# Optocoupler.net
KiCad netlist of a schematic drawn in Altium Designer
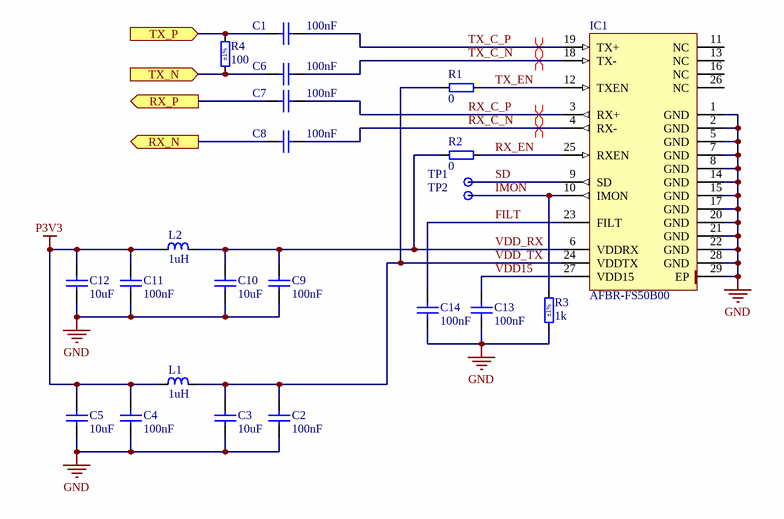
[diagram p0: Optocoupler.SchDoc]

(export (version "E")
  (design (tool "Eeschema 10.0.6"))
  (components
    (comp (ref "C1")
      (value "100nF")
      (footprint "CAPC1005X55N")
      (description "Non-polarised capacitor")
      (fields
        (field (name "PART NUMBER") "CC0402_100NF_50V_10%_X7R")
        (field (name "VOLTAGE") "50V")
        (field (name "AUTHOR") "CERN DEM MR")
      )
      (libsource (lib "Capacitors") (part "Capacitor - non polarized"))
    )
    (comp (ref "C2")
      (value "100nF")
      (footprint "CAPC1005X55N")
      (description "Non-polarised capacitor")
      (fields
        (field (name "PART NUMBER") "CC0402_100NF_50V_10%_X7R")
        (field (name "VOLTAGE") "50V")
        (field (name "AUTHOR") "CERN DEM MR")
      )
      (libsource (lib "Capacitors") (part "Capacitor - non polarized"))
    )
    (comp (ref "C3")
      (value "10uF")
      (footprint "CAPC1005X55N")
      (description "SMD Mulitlayer Ceramic Chip Capacitor")
      (fields
        (field (name "PART NUMBER") "CC0402_10UF_6.3V_20%_X5R")
        (field (name "VOLTAGE") "6.3V")
        (field (name "AUTHOR") "Michal Beldyga")
      )
      (libsource (lib "Capacitors") (part "Capacitor - non polarized"))
    )
    (comp (ref "C4")
      (value "100nF")
      (footprint "CAPC1005X55N")
      (description "Non-polarised capacitor")
      (fields
        (field (name "PART NUMBER") "CC0402_100NF_50V_10%_X7R")
        (field (name "VOLTAGE") "50V")
        (field (name "AUTHOR") "CERN DEM MR")
      )
      (libsource (lib "Capacitors") (part "Capacitor - non polarized"))
    )
    (comp (ref "C5")
      (value "10uF")
      (footprint "CAPC1005X55N")
      (description "SMD Mulitlayer Ceramic Chip Capacitor")
      (fields
        (field (name "PART NUMBER") "CC0402_10UF_6.3V_20%_X5R")
        (field (name "VOLTAGE") "6.3V")
        (field (name "AUTHOR") "Michal Beldyga")
      )
      (libsource (lib "Capacitors") (part "Capacitor - non polarized"))
    )
    (comp (ref "C6")
      (value "100nF")
      (footprint "CAPC1005X55N")
      (description "Non-polarised capacitor")
      (fields
        (field (name "PART NUMBER") "CC0402_100NF_50V_10%_X7R")
        (field (name "VOLTAGE") "50V")
        (field (name "AUTHOR") "CERN DEM MR")
      )
      (libsource (lib "Capacitors") (part "Capacitor - non polarized"))
    )
    (comp (ref "C7")
      (value "100nF")
      (footprint "CAPC1005X55N")
      (description "Non-polarised capacitor")
      (fields
        (field (name "PART NUMBER") "CC0402_100NF_50V_10%_X7R")
        (field (name "VOLTAGE") "50V")
        (field (name "AUTHOR") "CERN DEM MR")
      )
      (libsource (lib "Capacitors") (part "Capacitor - non polarized"))
    )
    (comp (ref "C8")
      (value "100nF")
      (footprint "CAPC1005X55N")
      (description "Non-polarised capacitor")
      (fields
        (field (name "PART NUMBER") "CC0402_100NF_50V_10%_X7R")
        (field (name "VOLTAGE") "50V")
        (field (name "AUTHOR") "CERN DEM MR")
      )
      (libsource (lib "Capacitors") (part "Capacitor - non polarized"))
    )
    (comp (ref "C9")
      (value "100nF")
      (footprint "CAPC1005X55N")
      (description "Non-polarised capacitor")
      (fields
        (field (name "PART NUMBER") "CC0402_100NF_50V_10%_X7R")
        (field (name "VOLTAGE") "50V")
        (field (name "AUTHOR") "CERN DEM MR")
      )
      (libsource (lib "Capacitors") (part "Capacitor - non polarized"))
    )
    (comp (ref "C10")
      (value "10uF")
      (footprint "CAPC1005X55N")
      (description "SMD Mulitlayer Ceramic Chip Capacitor")
      (fields
        (field (name "PART NUMBER") "CC0402_10UF_6.3V_20%_X5R")
        (field (name "VOLTAGE") "6.3V")
        (field (name "AUTHOR") "Michal Beldyga")
      )
      (libsource (lib "Capacitors") (part "Capacitor - non polarized"))
    )
    (comp (ref "C11")
      (value "100nF")
      (footprint "CAPC1005X55N")
      (description "Non-polarised capacitor")
      (fields
        (field (name "PART NUMBER") "CC0402_100NF_50V_10%_X7R")
        (field (name "VOLTAGE") "50V")
        (field (name "AUTHOR") "CERN DEM MR")
      )
      (libsource (lib "Capacitors") (part "Capacitor - non polarized"))
    )
    (comp (ref "C12")
      (value "10uF")
      (footprint "CAPC1005X55N")
      (description "SMD Mulitlayer Ceramic Chip Capacitor")
      (fields
        (field (name "PART NUMBER") "CC0402_10UF_6.3V_20%_X5R")
        (field (name "VOLTAGE") "6.3V")
        (field (name "AUTHOR") "Michal Beldyga")
      )
      (libsource (lib "Capacitors") (part "Capacitor - non polarized"))
    )
    (comp (ref "C13")
      (value "100nF")
      (footprint "CAPC1005X55N")
      (description "Non-polarised capacitor")
      (fields
        (field (name "PART NUMBER") "CC0402_100NF_50V_10%_X7R")
        (field (name "VOLTAGE") "50V")
        (field (name "AUTHOR") "CERN DEM MR")
      )
      (libsource (lib "Capacitors") (part "Capacitor - non polarized"))
    )
    (comp (ref "C14")
      (value "100nF")
      (footprint "CAPC1005X55N")
      (description "Non-polarised capacitor")
      (fields
        (field (name "PART NUMBER") "CC0402_100NF_50V_10%_X7R")
        (field (name "VOLTAGE") "50V")
        (field (name "AUTHOR") "CERN DEM MR")
      )
      (libsource (lib "Capacitors") (part "Capacitor - non polarized"))
    )
    (comp (ref "IC1")
      (value "AFBR-FS50B00")
      (footprint "BROADCOM_AFBR-FS50B00")
      (description "High Voltage Galvanic Insulation Link for DC to 5MBaud")
      (fields (field (name "MANUFACTURER") "BROADCOM") (field (name "AUTHOR") "CERN DEM HF"))
      (libsource (lib "ICs And Semiconductors") (part "AFBR-FS50B00"))
    )
    (comp (ref "L1")
      (value "1uH")
      (footprint "INDC1005X55N")
      (description "Inductor")
      (fields
        (field (name "PART NUMBER") "IND0402_1UH_5%_TDK_MLZ1005M1R0WT000")
        (field (name "TOLERANCE") "±20%")
        (field (name "AUTHOR") "Michal Beldyga")
      )
      (libsource (lib "Inductors Transformers") (part "Inductor"))
    )
    (comp (ref "L2")
      (value "1uH")
      (footprint "INDC1005X55N")
      (description "Inductor")
      (fields
        (field (name "PART NUMBER") "IND0402_1UH_5%_TDK_MLZ1005M1R0WT000")
        (field (name "TOLERANCE") "±20%")
        (field (name "AUTHOR") "Michal Beldyga")
      )
      (libsource (lib "Inductors Transformers") (part "Inductor"))
    )
    (comp (ref "R1")
      (value "0")
      (footprint "RESC1005X40N")
      (description "Resistor")
      (fields
        (field (name "PART NUMBER") "R0402_0R_JUMPER")
        (field (name "MANUFACTURER") "GENERIC")
        (field (name "AUTHOR") "CERN DEM JLC")
      )
      (libsource (lib "Resistors") (part "Resistor"))
    )
    (comp (ref "R2")
      (value "0")
      (footprint "RESC1005X40N")
      (description "Resistor")
      (fields
        (field (name "PART NUMBER") "R0402_0R_JUMPER")
        (field (name "MANUFACTURER") "GENERIC")
        (field (name "AUTHOR") "CERN DEM JLC")
      )
      (libsource (lib "Resistors") (part "Resistor"))
    )
    (comp (ref "R3")
      (value "1k")
      (footprint "RESC1005X40N")
      (description "Resistor - 1%")
      (fields
        (field (name "TOLERANCE") "±1%")
        (field (name "PART NUMBER") "R0402_1K_1%_0.0625W_100PPM")
        (field (name "POWER") "0.0625W")
        (field (name "AUTHOR") "CERN DEM JLC")
      )
      (libsource (lib "Resistors") (part "Resistor - 1%"))
    )
    (comp (ref "R4")
      (value "100")
      (footprint "RESC1005X40N")
      (description "Resistor - 1%")
      (fields
        (field (name "TOLERANCE") "±1%")
        (field (name "PART NUMBER") "R0402_100R_1%_0.1W_100PPM")
        (field (name "POWER") "0.1W")
        (field (name "AUTHOR") "CERN DEM JLC")
      )
      (libsource (lib "Resistors") (part "Resistor - 1%"))
    )
    (comp (ref "TP1")
      (value "Test Point")
      (footprint "TPS127")
      (fields (field (name "PART NUMBER") "SMD_PAD_1.27X1.27MM") (field (name "AUTHOR") "CERN DEM JLC"))
      (libsource (lib "Eletro-mechanical") (part "Test Point"))
    )
    (comp (ref "TP2")
      (value "Test Point")
      (footprint "TPS127")
      (fields (field (name "PART NUMBER") "SMD_PAD_1.27X1.27MM") (field (name "AUTHOR") "CERN DEM JLC"))
      (libsource (lib "Eletro-mechanical") (part "Test Point"))
    )
  )
  (nets
    (net (code "1") (name "/FILT") (class "Default")
      (node (ref "C14") (pin "2") (pinfunction "2_2") (pintype "passive"))
      (node (ref "IC1") (pin "23") (pinfunction "FILT_23") (pintype "passive"))
    )
    (net (code "2") (name "/IMON") (class "Default")
      (node (ref "IC1") (pin "10") (pinfunction "IMON_10") (pintype "output"))
      (node (ref "R3") (pin "2") (pinfunction "2_2") (pintype "passive"))
      (node (ref "TP2") (pin "1") (pinfunction "1_1") (pintype "bidirectional"))
    )
    (net (code "3") (name "/RX_C_N") (class "Default")
      (node (ref "C8") (pin "1") (pinfunction "1_1") (pintype "passive"))
      (node (ref "IC1") (pin "4") (pinfunction "RX-_4") (pintype "output"))
    )
    (net (code "4") (name "/RX_C_P") (class "Default")
      (node (ref "C7") (pin "1") (pinfunction "1_1") (pintype "passive"))
      (node (ref "IC1") (pin "3") (pinfunction "RX+_3") (pintype "output"))
    )
    (net (code "5") (name "/RX_EN") (class "Default")
      (node (ref "IC1") (pin "25") (pinfunction "RXEN_25") (pintype "input"))
      (node (ref "R2") (pin "2") (pinfunction "2_2") (pintype "passive"))
    )
    (net (code "6") (name "/RX_N") (class "Default")
      (node (ref "C8") (pin "2") (pinfunction "2_2") (pintype "passive"))
    )
    (net (code "7") (name "/RX_P") (class "Default")
      (node (ref "C7") (pin "2") (pinfunction "2_2") (pintype "passive"))
    )
    (net (code "8") (name "/SD") (class "Default")
      (node (ref "IC1") (pin "9") (pinfunction "SD_9") (pintype "output"))
      (node (ref "TP1") (pin "1") (pinfunction "1_1") (pintype "bidirectional"))
    )
    (net (code "9") (name "/TX_C_N") (class "Default")
      (node (ref "C6") (pin "1") (pinfunction "1_1") (pintype "passive"))
      (node (ref "IC1") (pin "18") (pinfunction "TX-_18") (pintype "input"))
    )
    (net (code "10") (name "/TX_C_P") (class "Default")
      (node (ref "C1") (pin "1") (pinfunction "1_1") (pintype "passive"))
      (node (ref "IC1") (pin "19") (pinfunction "TX+_19") (pintype "input"))
    )
    (net (code "11") (name "/TX_EN") (class "Default")
      (node (ref "IC1") (pin "12") (pinfunction "TXEN_12") (pintype "input"))
      (node (ref "R1") (pin "2") (pinfunction "2_2") (pintype "passive"))
    )
    (net (code "12") (name "/TX_N") (class "Default")
      (node (ref "C6") (pin "2") (pinfunction "2_2") (pintype "passive"))
      (node (ref "R4") (pin "1") (pinfunction "1_1") (pintype "passive"))
    )
    (net (code "13") (name "/TX_P") (class "Default")
      (node (ref "C1") (pin "2") (pinfunction "2_2") (pintype "passive"))
      (node (ref "R4") (pin "2") (pinfunction "2_2") (pintype "passive"))
    )
    (net (code "14") (name "/VDD15") (class "Default")
      (node (ref "C13") (pin "2") (pinfunction "2_2") (pintype "passive"))
      (node (ref "IC1") (pin "27") (pinfunction "VDD15_27") (pintype "power_in"))
    )
    (net (code "15") (name "/VDD_RX") (class "Default")
      (node (ref "C10") (pin "2") (pinfunction "2_2") (pintype "passive"))
      (node (ref "C9") (pin "2") (pinfunction "2_2") (pintype "passive"))
      (node (ref "IC1") (pin "6") (pinfunction "VDDRX_6") (pintype "power_in"))
      (node (ref "L2") (pin "1") (pinfunction "1_1") (pintype "passive"))
      (node (ref "R2") (pin "1") (pinfunction "1_1") (pintype "passive"))
    )
    (net (code "16") (name "/VDD_TX") (class "Default")
      (node (ref "C2") (pin "2") (pinfunction "2_2") (pintype "passive"))
      (node (ref "C3") (pin "2") (pinfunction "2_2") (pintype "passive"))
      (node (ref "IC1") (pin "24") (pinfunction "VDDTX_24") (pintype "power_in"))
      (node (ref "L1") (pin "1") (pinfunction "1_1") (pintype "passive"))
      (node (ref "R1") (pin "1") (pinfunction "1_1") (pintype "passive"))
    )
    (net (code "17") (name "GND") (class "Default")
      (node (ref "C10") (pin "1") (pinfunction "1_1") (pintype "passive"))
      (node (ref "C11") (pin "1") (pinfunction "1_1") (pintype "passive"))
      (node (ref "C12") (pin "1") (pinfunction "1_1") (pintype "passive"))
      (node (ref "C13") (pin "1") (pinfunction "1_1") (pintype "passive"))
      (node (ref "C14") (pin "1") (pinfunction "1_1") (pintype "passive"))
      (node (ref "C2") (pin "1") (pinfunction "1_1") (pintype "passive"))
      (node (ref "C3") (pin "1") (pinfunction "1_1") (pintype "passive"))
      (node (ref "C4") (pin "1") (pinfunction "1_1") (pintype "passive"))
      (node (ref "C5") (pin "1") (pinfunction "1_1") (pintype "passive"))
      (node (ref "C9") (pin "1") (pinfunction "1_1") (pintype "passive"))
      (node (ref "IC1") (pin "1") (pinfunction "GND_1") (pintype "power_in"))
      (node (ref "IC1") (pin "14") (pinfunction "GND_14") (pintype "power_in"))
      (node (ref "IC1") (pin "15") (pinfunction "GND_15") (pintype "power_in"))
      (node (ref "IC1") (pin "17") (pinfunction "GND_17") (pintype "power_in"))
      (node (ref "IC1") (pin "2") (pinfunction "GND_2") (pintype "power_in"))
      (node (ref "IC1") (pin "20") (pinfunction "GND_20") (pintype "power_in"))
      (node (ref "IC1") (pin "21") (pinfunction "GND_21") (pintype "power_in"))
      (node (ref "IC1") (pin "22") (pinfunction "GND_22") (pintype "power_in"))
      (node (ref "IC1") (pin "28") (pinfunction "GND_28") (pintype "power_in"))
      (node (ref "IC1") (pin "29") (pinfunction "EP_29") (pintype "power_in"))
      (node (ref "IC1") (pin "5") (pinfunction "GND_5") (pintype "power_in"))
      (node (ref "IC1") (pin "7") (pinfunction "GND_7") (pintype "power_in"))
      (node (ref "IC1") (pin "8") (pinfunction "GND_8") (pintype "power_in"))
      (node (ref "R3") (pin "1") (pinfunction "1_1") (pintype "passive"))
    )
    (net (code "18") (name "P3V3") (class "Default")
      (node (ref "C11") (pin "2") (pinfunction "2_2") (pintype "passive"))
      (node (ref "C12") (pin "2") (pinfunction "2_2") (pintype "passive"))
      (node (ref "C4") (pin "2") (pinfunction "2_2") (pintype "passive"))
      (node (ref "C5") (pin "2") (pinfunction "2_2") (pintype "passive"))
      (node (ref "L1") (pin "2") (pinfunction "2_2") (pintype "passive"))
      (node (ref "L2") (pin "2") (pinfunction "2_2") (pintype "passive"))
    )
    (net (code "19") (name "unconnected-(IC1-NC-Pad11)") (class "Default")
      (node (ref "IC1") (pin "11") (pinfunction "NC_11") (pintype "passive"))
    )
    (net (code "20") (name "unconnected-(IC1-NC-Pad13)") (class "Default")
      (node (ref "IC1") (pin "13") (pinfunction "NC_13") (pintype "passive"))
    )
    (net (code "21") (name "unconnected-(IC1-NC-Pad16)") (class "Default")
      (node (ref "IC1") (pin "16") (pinfunction "NC_16") (pintype "passive"))
    )
    (net (code "22") (name "unconnected-(IC1-NC-Pad26)") (class "Default")
      (node (ref "IC1") (pin "26") (pinfunction "NC_26") (pintype "passive"))
    )
  )
)
